# DP_eDP_Adapter_v2_0.net
KiCad netlist of a schematic drawn in EAGLE
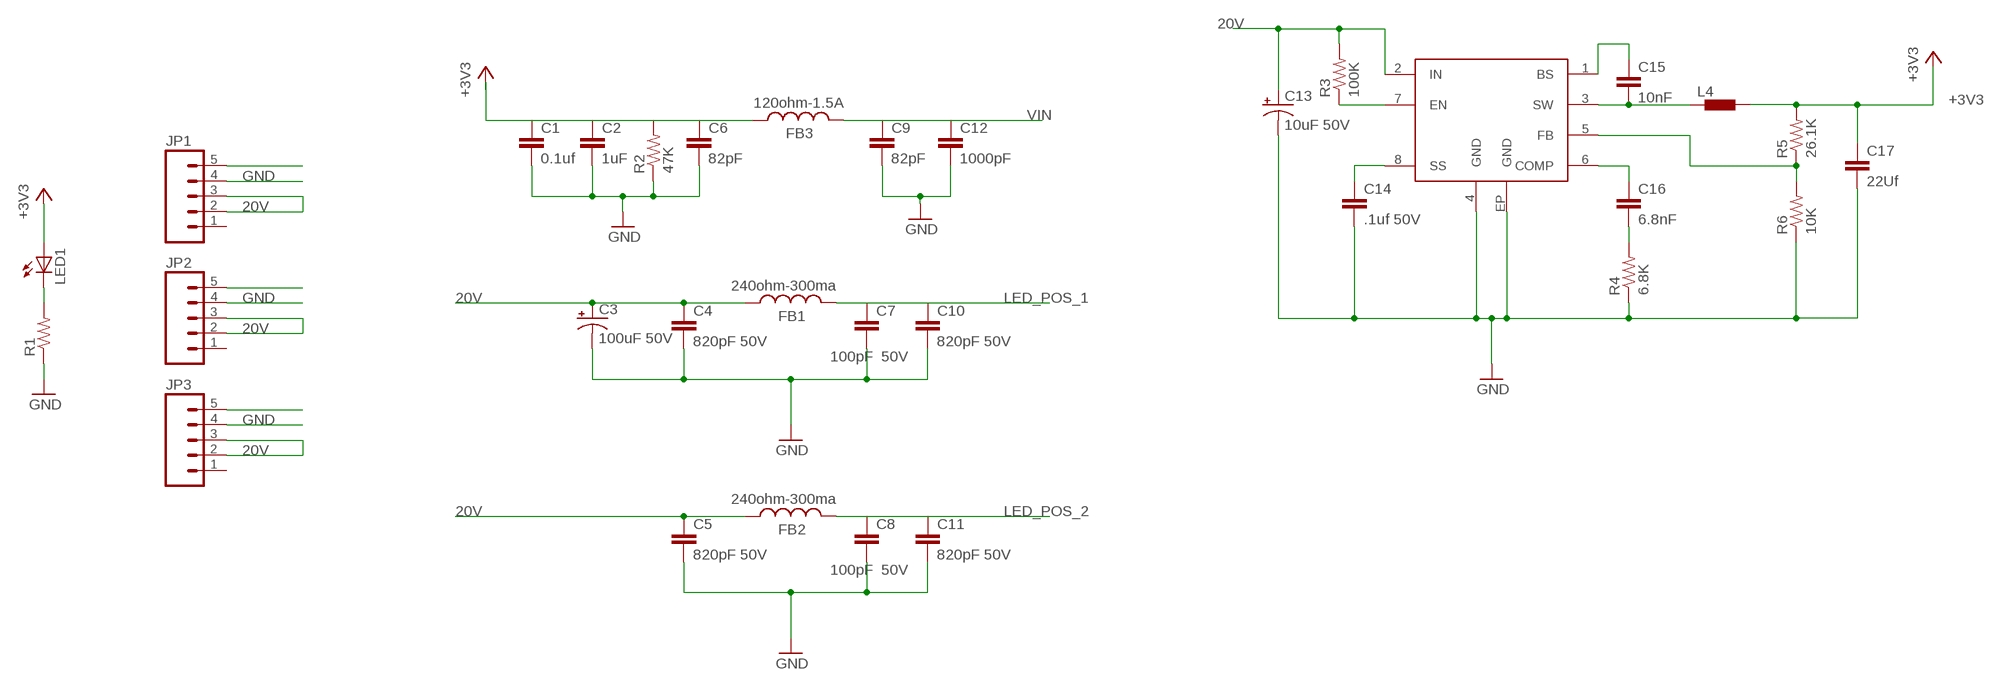
[diagram p0: schematic, sheet 1]
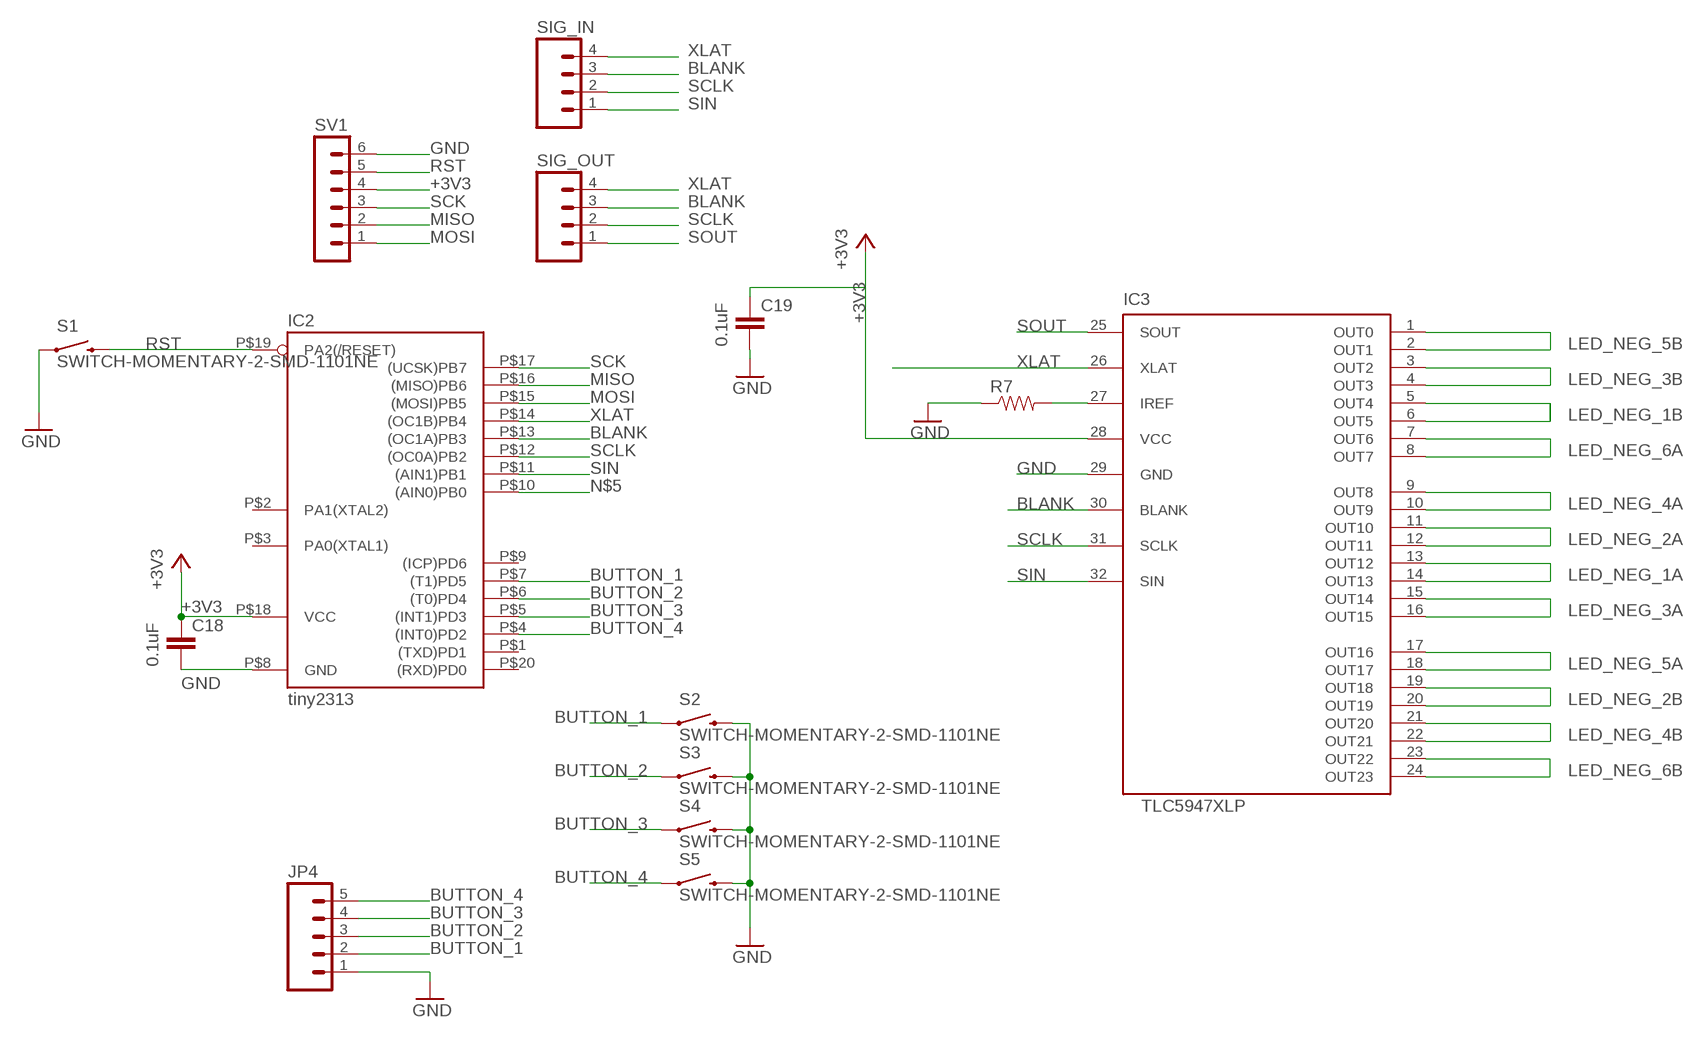
[diagram p1: schematic, sheet 2]
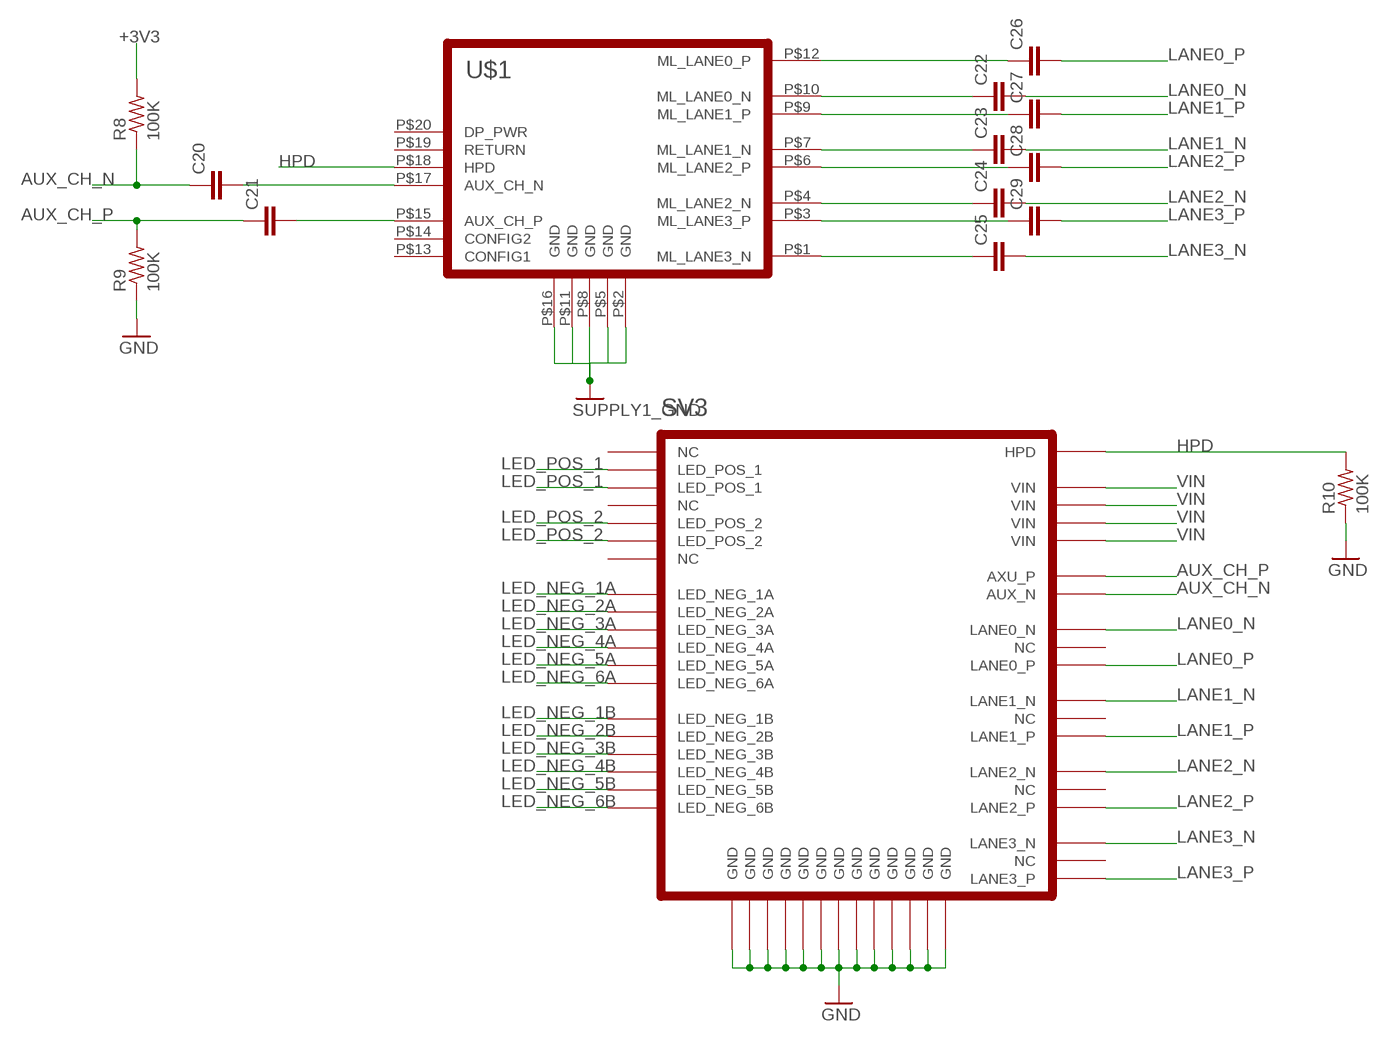
[diagram p2: schematic, sheet 3]

(export (version "E")
  (design (tool "Eeschema 10.0.6"))
  (components
    (comp (ref "C18")
      (value "0.1uF")
      (footprint "eagle-import:0402-CAP")
      (libsource (lib "eagle-import") (part "CAP0402-CAP"))
    )
    (comp (ref "C19")
      (value "0.1uF")
      (footprint "eagle-import:0402-CAP")
      (libsource (lib "eagle-import") (part "CAP0402-CAP"))
    )
    (comp (ref "IC2")
      (value "tiny2313")
      (footprint "eagle-import:MLF20")
      (libsource (lib "eagle-import") (part "TINY2313-M"))
    )
    (comp (ref "IC3")
      (value "TLC5947XLP")
      (footprint "eagle-import:QFN32_XLP")
      (libsource (lib "eagle-import") (part "TLC5947XLP"))
    )
    (comp (ref "JP4")
      (value "M05PTH")
      (footprint "eagle-import:1X05")
      (libsource (lib "eagle-import") (part "M05PTH"))
    )
    (comp (ref "R7")
      (value "RESISTOR0402-RES")
      (footprint "eagle-import:0402-RES")
      (libsource (lib "eagle-import") (part "RESISTOR0402-RES"))
    )
    (comp (ref "S1")
      (value "SWITCH-MOMENTARY-2-SMD-1101NE")
      (footprint "eagle-import:TACTILE-SWITCH-1101NE")
      (libsource (lib "eagle-import") (part "SWITCH-MOMENTARY-2-SMD-1101NE"))
    )
    (comp (ref "S2")
      (value "SWITCH-MOMENTARY-2-SMD-1101NE")
      (footprint "eagle-import:TACTILE-SWITCH-1101NE")
      (libsource (lib "eagle-import") (part "SWITCH-MOMENTARY-2-SMD-1101NE"))
    )
    (comp (ref "S3")
      (value "SWITCH-MOMENTARY-2-SMD-1101NE")
      (footprint "eagle-import:TACTILE-SWITCH-1101NE")
      (libsource (lib "eagle-import") (part "SWITCH-MOMENTARY-2-SMD-1101NE"))
    )
    (comp (ref "S4")
      (value "SWITCH-MOMENTARY-2-SMD-1101NE")
      (footprint "eagle-import:TACTILE-SWITCH-1101NE")
      (libsource (lib "eagle-import") (part "SWITCH-MOMENTARY-2-SMD-1101NE"))
    )
    (comp (ref "S5")
      (value "SWITCH-MOMENTARY-2-SMD-1101NE")
      (footprint "eagle-import:TACTILE-SWITCH-1101NE")
      (libsource (lib "eagle-import") (part "SWITCH-MOMENTARY-2-SMD-1101NE"))
    )
    (comp (ref "SIG_IN")
      (value "M04PTH")
      (footprint "eagle-import:1X04")
      (libsource (lib "eagle-import") (part "M04PTH"))
    )
    (comp (ref "SIG_OUT")
      (value "M04PTH")
      (footprint "eagle-import:1X04")
      (libsource (lib "eagle-import") (part "M04PTH"))
    )
    (comp (ref "SV1")
      (value "MA06-1")
      (footprint "eagle-import:MA06-1")
      (libsource (lib "eagle-import") (part "MA06-1"))
    )
    (comp (ref "C1")
      (value "0.1uf")
      (footprint "eagle-import:0402-CAP")
      (libsource (lib "eagle-import") (part "SparkFun-Passives_CAP0402-CAP"))
    )
    (comp (ref "C2")
      (value "1uF")
      (footprint "eagle-import:0402-CAP")
      (libsource (lib "eagle-import") (part "SparkFun-Passives_CAP0402-CAP"))
    )
    (comp (ref "C3")
      (value "100uF 50V")
      (footprint "eagle-import:EIA6032")
      (libsource (lib "eagle-import") (part "CAP_POL6032"))
    )
    (comp (ref "C4")
      (value "820pF 50V")
      (footprint "eagle-import:0402-CAP")
      (libsource (lib "eagle-import") (part "SparkFun-Passives_CAP0402-CAP"))
    )
    (comp (ref "C5")
      (value "820pF 50V")
      (footprint "eagle-import:0402-CAP")
      (libsource (lib "eagle-import") (part "SparkFun-Passives_CAP0402-CAP"))
    )
    (comp (ref "C6")
      (value "82pF")
      (footprint "eagle-import:0402-CAP")
      (libsource (lib "eagle-import") (part "SparkFun-Passives_CAP0402-CAP"))
    )
    (comp (ref "C7")
      (value "100pF 50V")
      (footprint "eagle-import:0402-CAP")
      (libsource (lib "eagle-import") (part "SparkFun-Passives_CAP0402-CAP"))
    )
    (comp (ref "C8")
      (value "100pF 50V")
      (footprint "eagle-import:0402-CAP")
      (libsource (lib "eagle-import") (part "SparkFun-Passives_CAP0402-CAP"))
    )
    (comp (ref "C9")
      (value "82pF")
      (footprint "eagle-import:0402-CAP")
      (libsource (lib "eagle-import") (part "SparkFun-Passives_CAP0402-CAP"))
    )
    (comp (ref "C10")
      (value "820pF 50V")
      (footprint "eagle-import:0402-CAP")
      (libsource (lib "eagle-import") (part "SparkFun-Passives_CAP0402-CAP"))
    )
    (comp (ref "C11")
      (value "820pF 50V")
      (footprint "eagle-import:0402-CAP")
      (libsource (lib "eagle-import") (part "SparkFun-Passives_CAP0402-CAP"))
    )
    (comp (ref "C12")
      (value "1000pF")
      (footprint "eagle-import:0402-CAP")
      (libsource (lib "eagle-import") (part "SparkFun-Passives_CAP0402-CAP"))
    )
    (comp (ref "C13")
      (value "10uF 50V")
      (footprint "eagle-import:EIA6032")
      (libsource (lib "eagle-import") (part "CAP_POL6032"))
    )
    (comp (ref "C14")
      (value ".1uf 50V")
      (footprint "eagle-import:0402-CAP")
      (libsource (lib "eagle-import") (part "SparkFun-Passives_CAP0402-CAP"))
    )
    (comp (ref "C15")
      (value "10nF")
      (footprint "eagle-import:1206")
      (libsource (lib "eagle-import") (part "SparkFun-Passives_CAP1206"))
    )
    (comp (ref "C16")
      (value "6.8nF")
      (footprint "eagle-import:0402-CAP")
      (libsource (lib "eagle-import") (part "SparkFun-Passives_CAP0402-CAP"))
    )
    (comp (ref "C17")
      (value "22Uf")
      (footprint "eagle-import:0805")
      (libsource (lib "eagle-import") (part "SparkFun-Passives_CAP0805"))
    )
    (comp (ref "FB1")
      (value "240ohm-300ma")
      (footprint "eagle-import:R0402")
      (libsource (lib "eagle-import") (part "L-US"))
    )
    (comp (ref "FB2")
      (value "240ohm-300ma")
      (footprint "eagle-import:R0402")
      (libsource (lib "eagle-import") (part "L-US"))
    )
    (comp (ref "FB3")
      (value "120ohm-1.5A")
      (footprint "eagle-import:R0402")
      (libsource (lib "eagle-import") (part "L-US"))
    )
    (comp (ref "IC1")
      (value "AP6502A")
      (footprint "eagle-import:SO8-EP")
      (libsource (lib "eagle-import") (part "AP6502A"))
    )
    (comp (ref "JP1")
      (value "M05PTH")
      (footprint "eagle-import:1X05")
      (libsource (lib "eagle-import") (part "M05PTH"))
    )
    (comp (ref "JP2")
      (value "M05PTH")
      (footprint "eagle-import:1X05")
      (libsource (lib "eagle-import") (part "M05PTH"))
    )
    (comp (ref "JP3")
      (value "M05PTH")
      (footprint "eagle-import:1X05")
      (libsource (lib "eagle-import") (part "M05PTH"))
    )
    (comp (ref "L4")
      (value "INDUCTORS_DR10300520C")
      (footprint "eagle-import:0520C")
      (libsource (lib "eagle-import") (part "INDUCTORS_DR10300520C"))
    )
    (comp (ref "LED1")
      (value "LED_LEDCHIPLED_1206")
      (footprint "eagle-import:LED_CHIPLED_1206")
      (libsource (lib "eagle-import") (part "LED_LEDCHIPLED_1206"))
    )
    (comp (ref "R1")
      (value "RESISTOR0402-RES")
      (footprint "eagle-import:0402-RES")
      (libsource (lib "eagle-import") (part "RESISTOR0402-RES"))
    )
    (comp (ref "R2")
      (value "47K")
      (footprint "eagle-import:0402-RES")
      (libsource (lib "eagle-import") (part "RESISTOR0402-RES"))
    )
    (comp (ref "R3")
      (value "100K")
      (footprint "eagle-import:0402-RES")
      (libsource (lib "eagle-import") (part "RESISTOR0402-RES"))
    )
    (comp (ref "R4")
      (value "6.8K")
      (footprint "eagle-import:0402-RES")
      (libsource (lib "eagle-import") (part "RESISTOR0402-RES"))
    )
    (comp (ref "R5")
      (value "26.1K")
      (footprint "eagle-import:0402-RES")
      (libsource (lib "eagle-import") (part "RESISTOR0402-RES"))
    )
    (comp (ref "R6")
      (value "10K")
      (footprint "eagle-import:0402-RES")
      (libsource (lib "eagle-import") (part "RESISTOR0402-RES"))
    )
    (comp (ref "C20")
      (value "SPARKFUN-PASSIVES_CAP0402-CAP")
      (footprint "eagle-import:SPARKFUN-PASSIVES_0402-CAP")
      (libsource (lib "eagle-import") (part "SPARKFUN-PASSIVES_CAP0402-CAP"))
    )
    (comp (ref "C21")
      (value "SPARKFUN-PASSIVES_CAP0402-CAP")
      (footprint "eagle-import:SPARKFUN-PASSIVES_0402-CAP")
      (libsource (lib "eagle-import") (part "SPARKFUN-PASSIVES_CAP0402-CAP"))
    )
    (comp (ref "C22")
      (value "SPARKFUN-PASSIVES_CAP0402-CAP")
      (footprint "eagle-import:SPARKFUN-PASSIVES_0402-CAP")
      (libsource (lib "eagle-import") (part "SPARKFUN-PASSIVES_CAP0402-CAP"))
    )
    (comp (ref "C23")
      (value "SPARKFUN-PASSIVES_CAP0402-CAP")
      (footprint "eagle-import:SPARKFUN-PASSIVES_0402-CAP")
      (libsource (lib "eagle-import") (part "SPARKFUN-PASSIVES_CAP0402-CAP"))
    )
    (comp (ref "C24")
      (value "SPARKFUN-PASSIVES_CAP0402-CAP")
      (footprint "eagle-import:SPARKFUN-PASSIVES_0402-CAP")
      (libsource (lib "eagle-import") (part "SPARKFUN-PASSIVES_CAP0402-CAP"))
    )
    (comp (ref "C25")
      (value "SPARKFUN-PASSIVES_CAP0402-CAP")
      (footprint "eagle-import:SPARKFUN-PASSIVES_0402-CAP")
      (libsource (lib "eagle-import") (part "SPARKFUN-PASSIVES_CAP0402-CAP"))
    )
    (comp (ref "C26")
      (value "SPARKFUN-PASSIVES_CAP0402-CAP")
      (footprint "eagle-import:SPARKFUN-PASSIVES_0402-CAP")
      (libsource (lib "eagle-import") (part "SPARKFUN-PASSIVES_CAP0402-CAP"))
    )
    (comp (ref "C27")
      (value "SPARKFUN-PASSIVES_CAP0402-CAP")
      (footprint "eagle-import:SPARKFUN-PASSIVES_0402-CAP")
      (libsource (lib "eagle-import") (part "SPARKFUN-PASSIVES_CAP0402-CAP"))
    )
    (comp (ref "C28")
      (value "SPARKFUN-PASSIVES_CAP0402-CAP")
      (footprint "eagle-import:SPARKFUN-PASSIVES_0402-CAP")
      (libsource (lib "eagle-import") (part "SPARKFUN-PASSIVES_CAP0402-CAP"))
    )
    (comp (ref "C29")
      (value "SPARKFUN-PASSIVES_CAP0402-CAP")
      (footprint "eagle-import:SPARKFUN-PASSIVES_0402-CAP")
      (libsource (lib "eagle-import") (part "SPARKFUN-PASSIVES_CAP0402-CAP"))
    )
    (comp (ref "R8")
      (value "100K")
      (footprint "eagle-import:R0402")
      (libsource (lib "eagle-import") (part "R-US_R0402"))
    )
    (comp (ref "R9")
      (value "100K")
      (footprint "eagle-import:R0402")
      (libsource (lib "eagle-import") (part "R-US_R0402"))
    )
    (comp (ref "R10")
      (value "100K")
      (footprint "eagle-import:R0402")
      (libsource (lib "eagle-import") (part "R-US_R0402"))
    )
    (comp (ref "SV3")
      (value "DP_EDP_ADAPTER_DP_EDP_ADAPTER_EDP_CONNECTOR")
      (footprint "eagle-import:DP_EDP_ADAPTER_DP_EDP_ADAPTER_EDP_MOLEX")
      (libsource (lib "eagle-import") (part "DP_EDP_ADAPTER_DP_EDP_ADAPTER_EDP_CONNECTOR"))
    )
    (comp (ref "U$1")
      (value "DP_EDP_ADAPTER_DP1RD20JQ2R400_SINK")
      (footprint "eagle-import:DP_EDP_ADAPTER_DP_REVERSE_JAE")
      (libsource (lib "eagle-import") (part "DP_EDP_ADAPTER_DP1RD20JQ2R400_SINK"))
    )
  )
  (nets
    (net (code "1") (name "+3V3") (class "Default")
      (node (ref "C1") (pin "1") (pinfunction "1_1") (pintype "passive"))
      (node (ref "C17") (pin "1") (pinfunction "1_1") (pintype "passive"))
      (node (ref "C18") (pin "1") (pinfunction "1_1") (pintype "passive"))
      (node (ref "C19") (pin "1") (pinfunction "1_1") (pintype "passive"))
      (node (ref "C2") (pin "1") (pinfunction "1_1") (pintype "passive"))
      (node (ref "C6") (pin "1") (pinfunction "1_1") (pintype "passive"))
      (node (ref "FB3") (pin "1") (pinfunction "1_1") (pintype "passive"))
      (node (ref "IC2") (pin "P$18") (pinfunction "VCC_P$18") (pintype "power_in"))
      (node (ref "IC3") (pin "28") (pinfunction "VCC_28") (pintype "bidirectional"))
      (node (ref "L4") (pin "P$2") (pinfunction "2_P$2") (pintype "passive"))
      (node (ref "LED1") (pin "A") (pinfunction "A_A") (pintype "passive"))
      (node (ref "R2") (pin "2") (pinfunction "2_2") (pintype "passive"))
      (node (ref "R5") (pin "2") (pinfunction "2_2") (pintype "passive"))
      (node (ref "R8") (pin "2") (pinfunction "2_2") (pintype "passive"))
      (node (ref "SV1") (pin "4") (pinfunction "4_4") (pintype "passive"))
    )
    (net (code "2") (name "20V") (class "Default")
      (node (ref "C13") (pin "P$1") (pinfunction "+_P$1") (pintype "passive"))
      (node (ref "C3") (pin "P$1") (pinfunction "+_P$1") (pintype "passive"))
      (node (ref "C4") (pin "1") (pinfunction "1_1") (pintype "passive"))
      (node (ref "C5") (pin "1") (pinfunction "1_1") (pintype "passive"))
      (node (ref "FB1") (pin "1") (pinfunction "1_1") (pintype "passive"))
      (node (ref "FB2") (pin "1") (pinfunction "1_1") (pintype "passive"))
      (node (ref "IC1") (pin "2") (pinfunction "IN_2") (pintype "bidirectional"))
      (node (ref "JP1") (pin "2") (pinfunction "2_2") (pintype "passive"))
      (node (ref "JP1") (pin "3") (pinfunction "3_3") (pintype "passive"))
      (node (ref "JP2") (pin "2") (pinfunction "2_2") (pintype "passive"))
      (node (ref "JP2") (pin "3") (pinfunction "3_3") (pintype "passive"))
      (node (ref "JP3") (pin "2") (pinfunction "2_2") (pintype "passive"))
      (node (ref "JP3") (pin "3") (pinfunction "3_3") (pintype "passive"))
      (node (ref "R3") (pin "2") (pinfunction "2_2") (pintype "passive"))
    )
    (net (code "3") (name "AUX_CH_N") (class "Default")
      (node (ref "C20") (pin "1") (pinfunction "1_1") (pintype "passive"))
      (node (ref "R8") (pin "1") (pinfunction "1_1") (pintype "passive"))
      (node (ref "SV3") (pin "P$10") (pinfunction "AUX_N_P$10") (pintype "bidirectional"))
    )
    (net (code "4") (name "AUX_CH_P") (class "Default")
      (node (ref "C21") (pin "1") (pinfunction "1_1") (pintype "passive"))
      (node (ref "R9") (pin "2") (pinfunction "2_2") (pintype "passive"))
      (node (ref "SV3") (pin "P$9") (pinfunction "AXU_P_P$9") (pintype "bidirectional"))
    )
    (net (code "5") (name "BLANK") (class "Default")
      (node (ref "IC2") (pin "P$13") (pinfunction "(OC1A)PB3_P$13") (pintype "bidirectional"))
      (node (ref "IC3") (pin "30") (pinfunction "BLANK_30") (pintype "bidirectional"))
      (node (ref "SIG_IN") (pin "3") (pinfunction "3_3") (pintype "passive"))
      (node (ref "SIG_OUT") (pin "3") (pinfunction "3_3") (pintype "passive"))
    )
    (net (code "6") (name "BUTTON_1") (class "Default")
      (node (ref "IC2") (pin "P$7") (pinfunction "(T1)PD5_P$7") (pintype "bidirectional"))
      (node (ref "JP4") (pin "2") (pinfunction "2_2") (pintype "passive"))
      (node (ref "S2") (pin "P$1") (pinfunction "1_P$1") (pintype "passive"))
    )
    (net (code "7") (name "BUTTON_2") (class "Default")
      (node (ref "IC2") (pin "P$6") (pinfunction "(T0)PD4_P$6") (pintype "bidirectional"))
      (node (ref "JP4") (pin "3") (pinfunction "3_3") (pintype "passive"))
      (node (ref "S3") (pin "P$1") (pinfunction "1_P$1") (pintype "passive"))
    )
    (net (code "8") (name "BUTTON_3") (class "Default")
      (node (ref "IC2") (pin "P$5") (pinfunction "(INT1)PD3_P$5") (pintype "bidirectional"))
      (node (ref "JP4") (pin "4") (pinfunction "4_4") (pintype "passive"))
      (node (ref "S4") (pin "P$1") (pinfunction "1_P$1") (pintype "passive"))
    )
    (net (code "9") (name "BUTTON_4") (class "Default")
      (node (ref "IC2") (pin "P$4") (pinfunction "(INT0)PD2_P$4") (pintype "bidirectional"))
      (node (ref "JP4") (pin "5") (pinfunction "5_5") (pintype "passive"))
      (node (ref "S5") (pin "P$1") (pinfunction "1_P$1") (pintype "passive"))
    )
    (net (code "10") (name "GND") (class "Default")
      (node (ref "C1") (pin "2") (pinfunction "2_2") (pintype "passive"))
      (node (ref "C10") (pin "2") (pinfunction "2_2") (pintype "passive"))
      (node (ref "C11") (pin "2") (pinfunction "2_2") (pintype "passive"))
      (node (ref "C12") (pin "2") (pinfunction "2_2") (pintype "passive"))
      (node (ref "C13") (pin "P$2") (pinfunction "-_P$2") (pintype "passive"))
      (node (ref "C14") (pin "2") (pinfunction "2_2") (pintype "passive"))
      (node (ref "C17") (pin "2") (pinfunction "2_2") (pintype "passive"))
      (node (ref "C18") (pin "2") (pinfunction "2_2") (pintype "passive"))
      (node (ref "C19") (pin "2") (pinfunction "2_2") (pintype "passive"))
      (node (ref "C2") (pin "2") (pinfunction "2_2") (pintype "passive"))
      (node (ref "C3") (pin "P$2") (pinfunction "-_P$2") (pintype "passive"))
      (node (ref "C4") (pin "2") (pinfunction "2_2") (pintype "passive"))
      (node (ref "C5") (pin "2") (pinfunction "2_2") (pintype "passive"))
      (node (ref "C6") (pin "2") (pinfunction "2_2") (pintype "passive"))
      (node (ref "C7") (pin "2") (pinfunction "2_2") (pintype "passive"))
      (node (ref "C8") (pin "2") (pinfunction "2_2") (pintype "passive"))
      (node (ref "C9") (pin "2") (pinfunction "2_2") (pintype "passive"))
      (node (ref "IC1") (pin "4") (pinfunction "GND_4") (pintype "bidirectional"))
      (node (ref "IC1") (pin "EP") (pinfunction "GND_EP") (pintype "bidirectional"))
      (node (ref "IC2") (pin "P$8") (pinfunction "GND_P$8") (pintype "power_in"))
      (node (ref "IC3") (pin "29") (pinfunction "GND_29") (pintype "bidirectional"))
      (node (ref "JP1") (pin "4") (pinfunction "4_4") (pintype "passive"))
      (node (ref "JP1") (pin "5") (pinfunction "5_5") (pintype "passive"))
      (node (ref "JP2") (pin "4") (pinfunction "4_4") (pintype "passive"))
      (node (ref "JP2") (pin "5") (pinfunction "5_5") (pintype "passive"))
      (node (ref "JP3") (pin "4") (pinfunction "4_4") (pintype "passive"))
      (node (ref "JP3") (pin "5") (pinfunction "5_5") (pintype "passive"))
      (node (ref "JP4") (pin "1") (pinfunction "1_1") (pintype "passive"))
      (node (ref "R1") (pin "1") (pinfunction "1_1") (pintype "passive"))
      (node (ref "R10") (pin "1") (pinfunction "1_1") (pintype "passive"))
      (node (ref "R2") (pin "1") (pinfunction "1_1") (pintype "passive"))
      (node (ref "R4") (pin "1") (pinfunction "1_1") (pintype "passive"))
      (node (ref "R6") (pin "1") (pinfunction "1_1") (pintype "passive"))
      (node (ref "R7") (pin "1") (pinfunction "1_1") (pintype "passive"))
      (node (ref "R9") (pin "1") (pinfunction "1_1") (pintype "passive"))
      (node (ref "S1") (pin "P$1") (pinfunction "1_P$1") (pintype "passive"))
      (node (ref "S2") (pin "P$2") (pinfunction "2_P$2") (pintype "passive"))
      (node (ref "S3") (pin "P$2") (pinfunction "2_P$2") (pintype "passive"))
      (node (ref "S4") (pin "P$2") (pinfunction "2_P$2") (pintype "passive"))
      (node (ref "S5") (pin "P$2") (pinfunction "2_P$2") (pintype "passive"))
      (node (ref "SV1") (pin "6") (pinfunction "6_6") (pintype "passive"))
      (node (ref "SV3") (pin "P$1") (pinfunction "GND_P$1") (pintype "bidirectional"))
      (node (ref "SV3") (pin "P$11") (pinfunction "GND_P$11") (pintype "bidirectional"))
      (node (ref "SV3") (pin "P$15") (pinfunction "GND_P$15") (pintype "bidirectional"))
      (node (ref "SV3") (pin "P$19") (pinfunction "GND_P$19") (pintype "bidirectional"))
      (node (ref "SV3") (pin "P$23") (pinfunction "GND_P$23") (pintype "bidirectional"))
      (node (ref "SV3") (pin "P$27") (pinfunction "GND_P$27") (pintype "bidirectional"))
      (node (ref "SV3") (pin "P$28") (pinfunction "GND_P$28") (pintype "bidirectional"))
      (node (ref "SV3") (pin "P$29") (pinfunction "GND_P$29") (pintype "bidirectional"))
      (node (ref "SV3") (pin "P$3") (pinfunction "GND_P$3") (pintype "bidirectional"))
      (node (ref "SV3") (pin "P$36") (pinfunction "GND_P$36") (pintype "bidirectional"))
      (node (ref "SV3") (pin "P$43") (pinfunction "GND_P$43") (pintype "bidirectional"))
      (node (ref "SV3") (pin "P$51") (pinfunction "GND_P$51") (pintype "bidirectional"))
      (node (ref "SV3") (pin "P$8") (pinfunction "GND_P$8") (pintype "bidirectional"))
      (node (ref "U$1") (pin "P$11") (pinfunction "GND_P$11") (pintype "bidirectional"))
      (node (ref "U$1") (pin "P$16") (pinfunction "GND_P$16") (pintype "bidirectional"))
      (node (ref "U$1") (pin "P$2") (pinfunction "GND_P$2") (pintype "bidirectional"))
      (node (ref "U$1") (pin "P$5") (pinfunction "GND_P$5") (pintype "bidirectional"))
      (node (ref "U$1") (pin "P$8") (pinfunction "GND_P$8") (pintype "bidirectional"))
    )
    (net (code "11") (name "HPD") (class "Default")
      (node (ref "R10") (pin "2") (pinfunction "2_2") (pintype "passive"))
      (node (ref "SV3") (pin "P$2") (pinfunction "HPD_P$2") (pintype "bidirectional"))
      (node (ref "U$1") (pin "P$18") (pinfunction "HPD_P$18") (pintype "bidirectional"))
    )
    (net (code "12") (name "LANE0_N") (class "Default")
      (node (ref "C22") (pin "2") (pinfunction "2_2") (pintype "passive"))
      (node (ref "SV3") (pin "P$12") (pinfunction "LANE0_N_P$12") (pintype "bidirectional"))
    )
    (net (code "13") (name "LANE0_P") (class "Default")
      (node (ref "C26") (pin "2") (pinfunction "2_2") (pintype "passive"))
      (node (ref "SV3") (pin "P$14") (pinfunction "LANE0_P_P$14") (pintype "bidirectional"))
    )
    (net (code "14") (name "LANE1_N") (class "Default")
      (node (ref "C23") (pin "2") (pinfunction "2_2") (pintype "passive"))
      (node (ref "SV3") (pin "P$16") (pinfunction "LANE1_N_P$16") (pintype "bidirectional"))
    )
    (net (code "15") (name "LANE1_P") (class "Default")
      (node (ref "C27") (pin "2") (pinfunction "2_2") (pintype "passive"))
      (node (ref "SV3") (pin "P$18") (pinfunction "LANE1_P_P$18") (pintype "bidirectional"))
    )
    (net (code "16") (name "LANE2_N") (class "Default")
      (node (ref "C24") (pin "2") (pinfunction "2_2") (pintype "passive"))
      (node (ref "SV3") (pin "P$20") (pinfunction "LANE2_N_P$20") (pintype "bidirectional"))
    )
    (net (code "17") (name "LANE2_P") (class "Default")
      (node (ref "C28") (pin "2") (pinfunction "2_2") (pintype "passive"))
      (node (ref "SV3") (pin "P$22") (pinfunction "LANE2_P_P$22") (pintype "bidirectional"))
    )
    (net (code "18") (name "LANE3_N") (class "Default")
      (node (ref "C25") (pin "2") (pinfunction "2_2") (pintype "passive"))
      (node (ref "SV3") (pin "P$24") (pinfunction "LANE3_N_P$24") (pintype "bidirectional"))
    )
    (net (code "19") (name "LANE3_P") (class "Default")
      (node (ref "C29") (pin "2") (pinfunction "2_2") (pintype "passive"))
      (node (ref "SV3") (pin "P$26") (pinfunction "LANE3_P_P$26") (pintype "bidirectional"))
    )
    (net (code "20") (name "LED_NEG_1A") (class "Default")
      (node (ref "IC3") (pin "13") (pinfunction "OUT12_13") (pintype "bidirectional"))
      (node (ref "IC3") (pin "14") (pinfunction "OUT13_14") (pintype "bidirectional"))
      (node (ref "SV3") (pin "P$42") (pinfunction "LED_NEG_1A_P$42") (pintype "bidirectional"))
    )
    (net (code "21") (name "LED_NEG_1B") (class "Default")
      (node (ref "IC3") (pin "5") (pinfunction "OUT4_5") (pintype "bidirectional"))
      (node (ref "IC3") (pin "6") (pinfunction "OUT5_6") (pintype "bidirectional"))
      (node (ref "SV3") (pin "P$35") (pinfunction "LED_NEG_1B_P$35") (pintype "bidirectional"))
    )
    (net (code "22") (name "LED_NEG_2A") (class "Default")
      (node (ref "IC3") (pin "11") (pinfunction "OUT10_11") (pintype "bidirectional"))
      (node (ref "IC3") (pin "12") (pinfunction "OUT11_12") (pintype "bidirectional"))
      (node (ref "SV3") (pin "P$41") (pinfunction "LED_NEG_2A_P$41") (pintype "bidirectional"))
    )
    (net (code "23") (name "LED_NEG_2B") (class "Default")
      (node (ref "IC3") (pin "19") (pinfunction "OUT18_19") (pintype "bidirectional"))
      (node (ref "IC3") (pin "20") (pinfunction "OUT19_20") (pintype "bidirectional"))
      (node (ref "SV3") (pin "P$34") (pinfunction "LED_NEG_2B_P$34") (pintype "bidirectional"))
    )
    (net (code "24") (name "LED_NEG_3A") (class "Default")
      (node (ref "IC3") (pin "15") (pinfunction "OUT14_15") (pintype "bidirectional"))
      (node (ref "IC3") (pin "16") (pinfunction "OUT15_16") (pintype "bidirectional"))
      (node (ref "SV3") (pin "P$40") (pinfunction "LED_NEG_3A_P$40") (pintype "bidirectional"))
    )
    (net (code "25") (name "LED_NEG_3B") (class "Default")
      (node (ref "IC3") (pin "3") (pinfunction "OUT2_3") (pintype "bidirectional"))
      (node (ref "IC3") (pin "4") (pinfunction "OUT3_4") (pintype "bidirectional"))
      (node (ref "SV3") (pin "P$33") (pinfunction "LED_NEG_3B_P$33") (pintype "bidirectional"))
    )
    (net (code "26") (name "LED_NEG_4A") (class "Default")
      (node (ref "IC3") (pin "10") (pinfunction "OUT9_10") (pintype "bidirectional"))
      (node (ref "IC3") (pin "9") (pinfunction "OUT8_9") (pintype "bidirectional"))
      (node (ref "SV3") (pin "P$39") (pinfunction "LED_NEG_4A_P$39") (pintype "bidirectional"))
    )
    (net (code "27") (name "LED_NEG_4B") (class "Default")
      (node (ref "IC3") (pin "21") (pinfunction "OUT20_21") (pintype "bidirectional"))
      (node (ref "IC3") (pin "22") (pinfunction "OUT21_22") (pintype "bidirectional"))
      (node (ref "SV3") (pin "P$32") (pinfunction "LED_NEG_4B_P$32") (pintype "bidirectional"))
    )
    (net (code "28") (name "LED_NEG_5A") (class "Default")
      (node (ref "IC3") (pin "17") (pinfunction "OUT16_17") (pintype "bidirectional"))
      (node (ref "IC3") (pin "18") (pinfunction "OUT17_18") (pintype "bidirectional"))
      (node (ref "SV3") (pin "P$38") (pinfunction "LED_NEG_5A_P$38") (pintype "bidirectional"))
    )
    (net (code "29") (name "LED_NEG_5B") (class "Default")
      (node (ref "IC3") (pin "1") (pinfunction "OUT0_1") (pintype "bidirectional"))
      (node (ref "IC3") (pin "2") (pinfunction "OUT1_2") (pintype "bidirectional"))
      (node (ref "SV3") (pin "P$31") (pinfunction "LED_NEG_5B_P$31") (pintype "bidirectional"))
    )
    (net (code "30") (name "LED_NEG_6A") (class "Default")
      (node (ref "IC3") (pin "7") (pinfunction "OUT6_7") (pintype "bidirectional"))
      (node (ref "IC3") (pin "8") (pinfunction "OUT7_8") (pintype "bidirectional"))
      (node (ref "SV3") (pin "P$37") (pinfunction "LED_NEG_6A_P$37") (pintype "bidirectional"))
    )
    (net (code "31") (name "LED_NEG_6B") (class "Default")
      (node (ref "IC3") (pin "23") (pinfunction "OUT22_23") (pintype "bidirectional"))
      (node (ref "IC3") (pin "24") (pinfunction "OUT23_24") (pintype "bidirectional"))
      (node (ref "SV3") (pin "P$30") (pinfunction "LED_NEG_6B_P$30") (pintype "bidirectional"))
    )
    (net (code "32") (name "LED_POS_1") (class "Default")
      (node (ref "C10") (pin "1") (pinfunction "1_1") (pintype "passive"))
      (node (ref "C7") (pin "1") (pinfunction "1_1") (pintype "passive"))
      (node (ref "FB1") (pin "2") (pinfunction "2_2") (pintype "passive"))
      (node (ref "SV3") (pin "P$48") (pinfunction "LED_POS_1_P$48") (pintype "bidirectional"))
      (node (ref "SV3") (pin "P$49") (pinfunction "LED_POS_1_P$49") (pintype "bidirectional"))
    )
    (net (code "33") (name "LED_POS_2") (class "Default")
      (node (ref "C11") (pin "1") (pinfunction "1_1") (pintype "passive"))
      (node (ref "C8") (pin "1") (pinfunction "1_1") (pintype "passive"))
      (node (ref "FB2") (pin "2") (pinfunction "2_2") (pintype "passive"))
      (node (ref "SV3") (pin "P$45") (pinfunction "LED_POS_2_P$45") (pintype "bidirectional"))
      (node (ref "SV3") (pin "P$46") (pinfunction "LED_POS_2_P$46") (pintype "bidirectional"))
    )
    (net (code "34") (name "MISO") (class "Default")
      (node (ref "IC2") (pin "P$16") (pinfunction "(MISO)PB6_P$16") (pintype "bidirectional"))
      (node (ref "SV1") (pin "2") (pinfunction "2_2") (pintype "passive"))
    )
    (net (code "35") (name "MOSI") (class "Default")
      (node (ref "IC2") (pin "P$15") (pinfunction "(MOSI)PB5_P$15") (pintype "bidirectional"))
      (node (ref "SV1") (pin "1") (pinfunction "1_1") (pintype "passive"))
    )
    (net (code "36") (name "N$5") (class "Default")
      (node (ref "IC2") (pin "P$10") (pinfunction "(AIN0)PB0_P$10") (pintype "bidirectional"))
    )
    (net (code "37") (name "Net-(C16-Pad2)") (class "Default")
      (node (ref "C16") (pin "2") (pinfunction "2_2") (pintype "passive"))
      (node (ref "R4") (pin "2") (pinfunction "2_2") (pintype "passive"))
    )
    (net (code "38") (name "Net-(IC1-BS)") (class "Default")
      (node (ref "C15") (pin "1") (pinfunction "1_1") (pintype "passive"))
      (node (ref "IC1") (pin "1") (pinfunction "BS_1") (pintype "bidirectional"))
    )
    (net (code "39") (name "Net-(IC1-COMP)") (class "Default")
      (node (ref "C16") (pin "1") (pinfunction "1_1") (pintype "passive"))
      (node (ref "IC1") (pin "6") (pinfunction "COMP_6") (pintype "bidirectional"))
    )
    (net (code "40") (name "Net-(IC1-EN)") (class "Default")
      (node (ref "IC1") (pin "7") (pinfunction "EN_7") (pintype "bidirectional"))
      (node (ref "R3") (pin "1") (pinfunction "1_1") (pintype "passive"))
    )
    (net (code "41") (name "Net-(IC1-FB)") (class "Default")
      (node (ref "IC1") (pin "5") (pinfunction "FB_5") (pintype "bidirectional"))
      (node (ref "R5") (pin "1") (pinfunction "1_1") (pintype "passive"))
      (node (ref "R6") (pin "2") (pinfunction "2_2") (pintype "passive"))
    )
    (net (code "42") (name "Net-(IC1-SS)") (class "Default")
      (node (ref "C14") (pin "1") (pinfunction "1_1") (pintype "passive"))
      (node (ref "IC1") (pin "8") (pinfunction "SS_8") (pintype "bidirectional"))
    )
    (net (code "43") (name "Net-(IC1-SW)") (class "Default")
      (node (ref "C15") (pin "2") (pinfunction "2_2") (pintype "passive"))
      (node (ref "IC1") (pin "3") (pinfunction "SW_3") (pintype "bidirectional"))
      (node (ref "L4") (pin "P$1") (pinfunction "1_P$1") (pintype "passive"))
    )
    (net (code "44") (name "Net-(IC3-IREF)") (class "Default")
      (node (ref "IC3") (pin "27") (pinfunction "IREF_27") (pintype "bidirectional"))
      (node (ref "R7") (pin "2") (pinfunction "2_2") (pintype "passive"))
    )
    (net (code "45") (name "Net-(LED1-PadC)") (class "Default")
      (node (ref "LED1") (pin "C") (pinfunction "C_C") (pintype "passive"))
      (node (ref "R1") (pin "2") (pinfunction "2_2") (pintype "passive"))
    )
    (net (code "46") (name "Net-(U$1-AUX_CH_N)") (class "Default")
      (node (ref "C20") (pin "2") (pinfunction "2_2") (pintype "passive"))
      (node (ref "U$1") (pin "P$17") (pinfunction "AUX_CH_N_P$17") (pintype "bidirectional"))
    )
    (net (code "47") (name "Net-(U$1-AUX_CH_P)") (class "Default")
      (node (ref "C21") (pin "2") (pinfunction "2_2") (pintype "passive"))
      (node (ref "U$1") (pin "P$15") (pinfunction "AUX_CH_P_P$15") (pintype "bidirectional"))
    )
    (net (code "48") (name "Net-(U$1-ML_LANE0_N)") (class "Default")
      (node (ref "C22") (pin "1") (pinfunction "1_1") (pintype "passive"))
      (node (ref "U$1") (pin "P$10") (pinfunction "ML_LANE0_N_P$10") (pintype "bidirectional"))
    )
    (net (code "49") (name "Net-(U$1-ML_LANE0_P)") (class "Default")
      (node (ref "C26") (pin "1") (pinfunction "1_1") (pintype "passive"))
      (node (ref "U$1") (pin "P$12") (pinfunction "ML_LANE0_P_P$12") (pintype "bidirectional"))
    )
    (net (code "50") (name "Net-(U$1-ML_LANE1_N)") (class "Default")
      (node (ref "C23") (pin "1") (pinfunction "1_1") (pintype "passive"))
      (node (ref "U$1") (pin "P$7") (pinfunction "ML_LANE1_N_P$7") (pintype "bidirectional"))
    )
    (net (code "51") (name "Net-(U$1-ML_LANE1_P)") (class "Default")
      (node (ref "C27") (pin "1") (pinfunction "1_1") (pintype "passive"))
      (node (ref "U$1") (pin "P$9") (pinfunction "ML_LANE1_P_P$9") (pintype "bidirectional"))
    )
    (net (code "52") (name "Net-(U$1-ML_LANE2_N)") (class "Default")
      (node (ref "C24") (pin "1") (pinfunction "1_1") (pintype "passive"))
      (node (ref "U$1") (pin "P$4") (pinfunction "ML_LANE2_N_P$4") (pintype "bidirectional"))
    )
    (net (code "53") (name "Net-(U$1-ML_LANE2_P)") (class "Default")
      (node (ref "C28") (pin "1") (pinfunction "1_1") (pintype "passive"))
      (node (ref "U$1") (pin "P$6") (pinfunction "ML_LANE2_P_P$6") (pintype "bidirectional"))
    )
    (net (code "54") (name "Net-(U$1-ML_LANE3_N)") (class "Default")
      (node (ref "C25") (pin "1") (pinfunction "1_1") (pintype "passive"))
      (node (ref "U$1") (pin "P$1") (pinfunction "ML_LANE3_N_P$1") (pintype "bidirectional"))
    )
    (net (code "55") (name "Net-(U$1-ML_LANE3_P)") (class "Default")
      (node (ref "C29") (pin "1") (pinfunction "1_1") (pintype "passive"))
      (node (ref "U$1") (pin "P$3") (pinfunction "ML_LANE3_P_P$3") (pintype "bidirectional"))
    )
    (net (code "56") (name "RST") (class "Default")
      (node (ref "IC2") (pin "P$19") (pinfunction "PA2(/RESET)_P$19") (pintype "input"))
      (node (ref "S1") (pin "P$2") (pinfunction "2_P$2") (pintype "passive"))
      (node (ref "SV1") (pin "5") (pinfunction "5_5") (pintype "passive"))
    )
    (net (code "57") (name "SCK") (class "Default")
      (node (ref "IC2") (pin "P$17") (pinfunction "(UCSK)PB7_P$17") (pintype "bidirectional"))
      (node (ref "SV1") (pin "3") (pinfunction "3_3") (pintype "passive"))
    )
    (net (code "58") (name "SCLK") (class "Default")
      (node (ref "IC2") (pin "P$12") (pinfunction "(OC0A)PB2_P$12") (pintype "bidirectional"))
      (node (ref "IC3") (pin "31") (pinfunction "SCLK_31") (pintype "bidirectional"))
      (node (ref "SIG_IN") (pin "2") (pinfunction "2_2") (pintype "passive"))
      (node (ref "SIG_OUT") (pin "2") (pinfunction "2_2") (pintype "passive"))
    )
    (net (code "59") (name "SIN") (class "Default")
      (node (ref "IC2") (pin "P$11") (pinfunction "(AIN1)PB1_P$11") (pintype "bidirectional"))
      (node (ref "IC3") (pin "32") (pinfunction "SIN_32") (pintype "bidirectional"))
      (node (ref "SIG_IN") (pin "1") (pinfunction "1_1") (pintype "passive"))
    )
    (net (code "60") (name "SOUT") (class "Default")
      (node (ref "IC3") (pin "25") (pinfunction "SOUT_25") (pintype "bidirectional"))
      (node (ref "SIG_OUT") (pin "1") (pinfunction "1_1") (pintype "passive"))
    )
    (net (code "61") (name "VIN") (class "Default")
      (node (ref "C12") (pin "1") (pinfunction "1_1") (pintype "passive"))
      (node (ref "C9") (pin "1") (pinfunction "1_1") (pintype "passive"))
      (node (ref "FB3") (pin "2") (pinfunction "2_2") (pintype "passive"))
      (node (ref "SV3") (pin "P$4") (pinfunction "VIN_P$4") (pintype "bidirectional"))
      (node (ref "SV3") (pin "P$5") (pinfunction "VIN_P$5") (pintype "bidirectional"))
      (node (ref "SV3") (pin "P$6") (pinfunction "VIN_P$6") (pintype "bidirectional"))
      (node (ref "SV3") (pin "P$7") (pinfunction "VIN_P$7") (pintype "bidirectional"))
    )
    (net (code "62") (name "XLAT") (class "Default")
      (node (ref "IC2") (pin "P$14") (pinfunction "(OC1B)PB4_P$14") (pintype "bidirectional"))
      (node (ref "IC3") (pin "26") (pinfunction "XLAT_26") (pintype "bidirectional"))
      (node (ref "SIG_IN") (pin "4") (pinfunction "4_4") (pintype "passive"))
      (node (ref "SIG_OUT") (pin "4") (pinfunction "4_4") (pintype "passive"))
    )
    (net (code "63") (name "unconnected-(IC2-(ICP)PD6-PadP$9)") (class "Default")
      (node (ref "IC2") (pin "P$9") (pinfunction "(ICP)PD6_P$9") (pintype "bidirectional"))
    )
    (net (code "64") (name "unconnected-(IC2-(RXD)PD0-PadP$20)") (class "Default")
      (node (ref "IC2") (pin "P$20") (pinfunction "(RXD)PD0_P$20") (pintype "bidirectional"))
    )
    (net (code "65") (name "unconnected-(IC2-(TXD)PD1-PadP$1)") (class "Default")
      (node (ref "IC2") (pin "P$1") (pinfunction "(TXD)PD1_P$1") (pintype "bidirectional"))
    )
    (net (code "66") (name "unconnected-(IC2-PA0(XTAL1)-PadP$3)") (class "Default")
      (node (ref "IC2") (pin "P$3") (pinfunction "PA0(XTAL1)_P$3") (pintype "bidirectional"))
    )
    (net (code "67") (name "unconnected-(IC2-PA1(XTAL2)-PadP$2)") (class "Default")
      (node (ref "IC2") (pin "P$2") (pinfunction "PA1(XTAL2)_P$2") (pintype "bidirectional"))
    )
    (net (code "68") (name "unconnected-(JP1-Pad1)") (class "Default")
      (node (ref "JP1") (pin "1") (pinfunction "1_1") (pintype "passive"))
    )
    (net (code "69") (name "unconnected-(JP2-Pad1)") (class "Default")
      (node (ref "JP2") (pin "1") (pinfunction "1_1") (pintype "passive"))
    )
    (net (code "70") (name "unconnected-(JP3-Pad1)") (class "Default")
      (node (ref "JP3") (pin "1") (pinfunction "1_1") (pintype "passive"))
    )
    (net (code "71") (name "unconnected-(SV3-NC-PadP$13)") (class "Default")
      (node (ref "SV3") (pin "P$13") (pinfunction "NC_P$13") (pintype "bidirectional"))
    )
    (net (code "72") (name "unconnected-(SV3-NC-PadP$17)") (class "Default")
      (node (ref "SV3") (pin "P$17") (pinfunction "NC_P$17") (pintype "bidirectional"))
    )
    (net (code "73") (name "unconnected-(SV3-NC-PadP$21)") (class "Default")
      (node (ref "SV3") (pin "P$21") (pinfunction "NC_P$21") (pintype "bidirectional"))
    )
    (net (code "74") (name "unconnected-(SV3-NC-PadP$25)") (class "Default")
      (node (ref "SV3") (pin "P$25") (pinfunction "NC_P$25") (pintype "bidirectional"))
    )
    (net (code "75") (name "unconnected-(SV3-NC-PadP$44)") (class "Default")
      (node (ref "SV3") (pin "P$44") (pinfunction "NC_P$44") (pintype "bidirectional"))
    )
    (net (code "76") (name "unconnected-(SV3-NC-PadP$47)") (class "Default")
      (node (ref "SV3") (pin "P$47") (pinfunction "NC_P$47") (pintype "bidirectional"))
    )
    (net (code "77") (name "unconnected-(SV3-NC-PadP$50)") (class "Default")
      (node (ref "SV3") (pin "P$50") (pinfunction "NC_P$50") (pintype "bidirectional"))
    )
    (net (code "78") (name "unconnected-(U$1-CONFIG1-PadP$13)") (class "Default")
      (node (ref "U$1") (pin "P$13") (pinfunction "CONFIG1_P$13") (pintype "bidirectional"))
    )
    (net (code "79") (name "unconnected-(U$1-CONFIG2-PadP$14)") (class "Default")
      (node (ref "U$1") (pin "P$14") (pinfunction "CONFIG2_P$14") (pintype "bidirectional"))
    )
    (net (code "80") (name "unconnected-(U$1-DP_PWR-PadP$20)") (class "Default")
      (node (ref "U$1") (pin "P$20") (pinfunction "DP_PWR_P$20") (pintype "bidirectional"))
    )
    (net (code "81") (name "unconnected-(U$1-RETURN-PadP$19)") (class "Default")
      (node (ref "U$1") (pin "P$19") (pinfunction "RETURN_P$19") (pintype "bidirectional"))
    )
  )
)
